# 09_Misc.net
KiCad netlist of a schematic drawn in Altium Designer
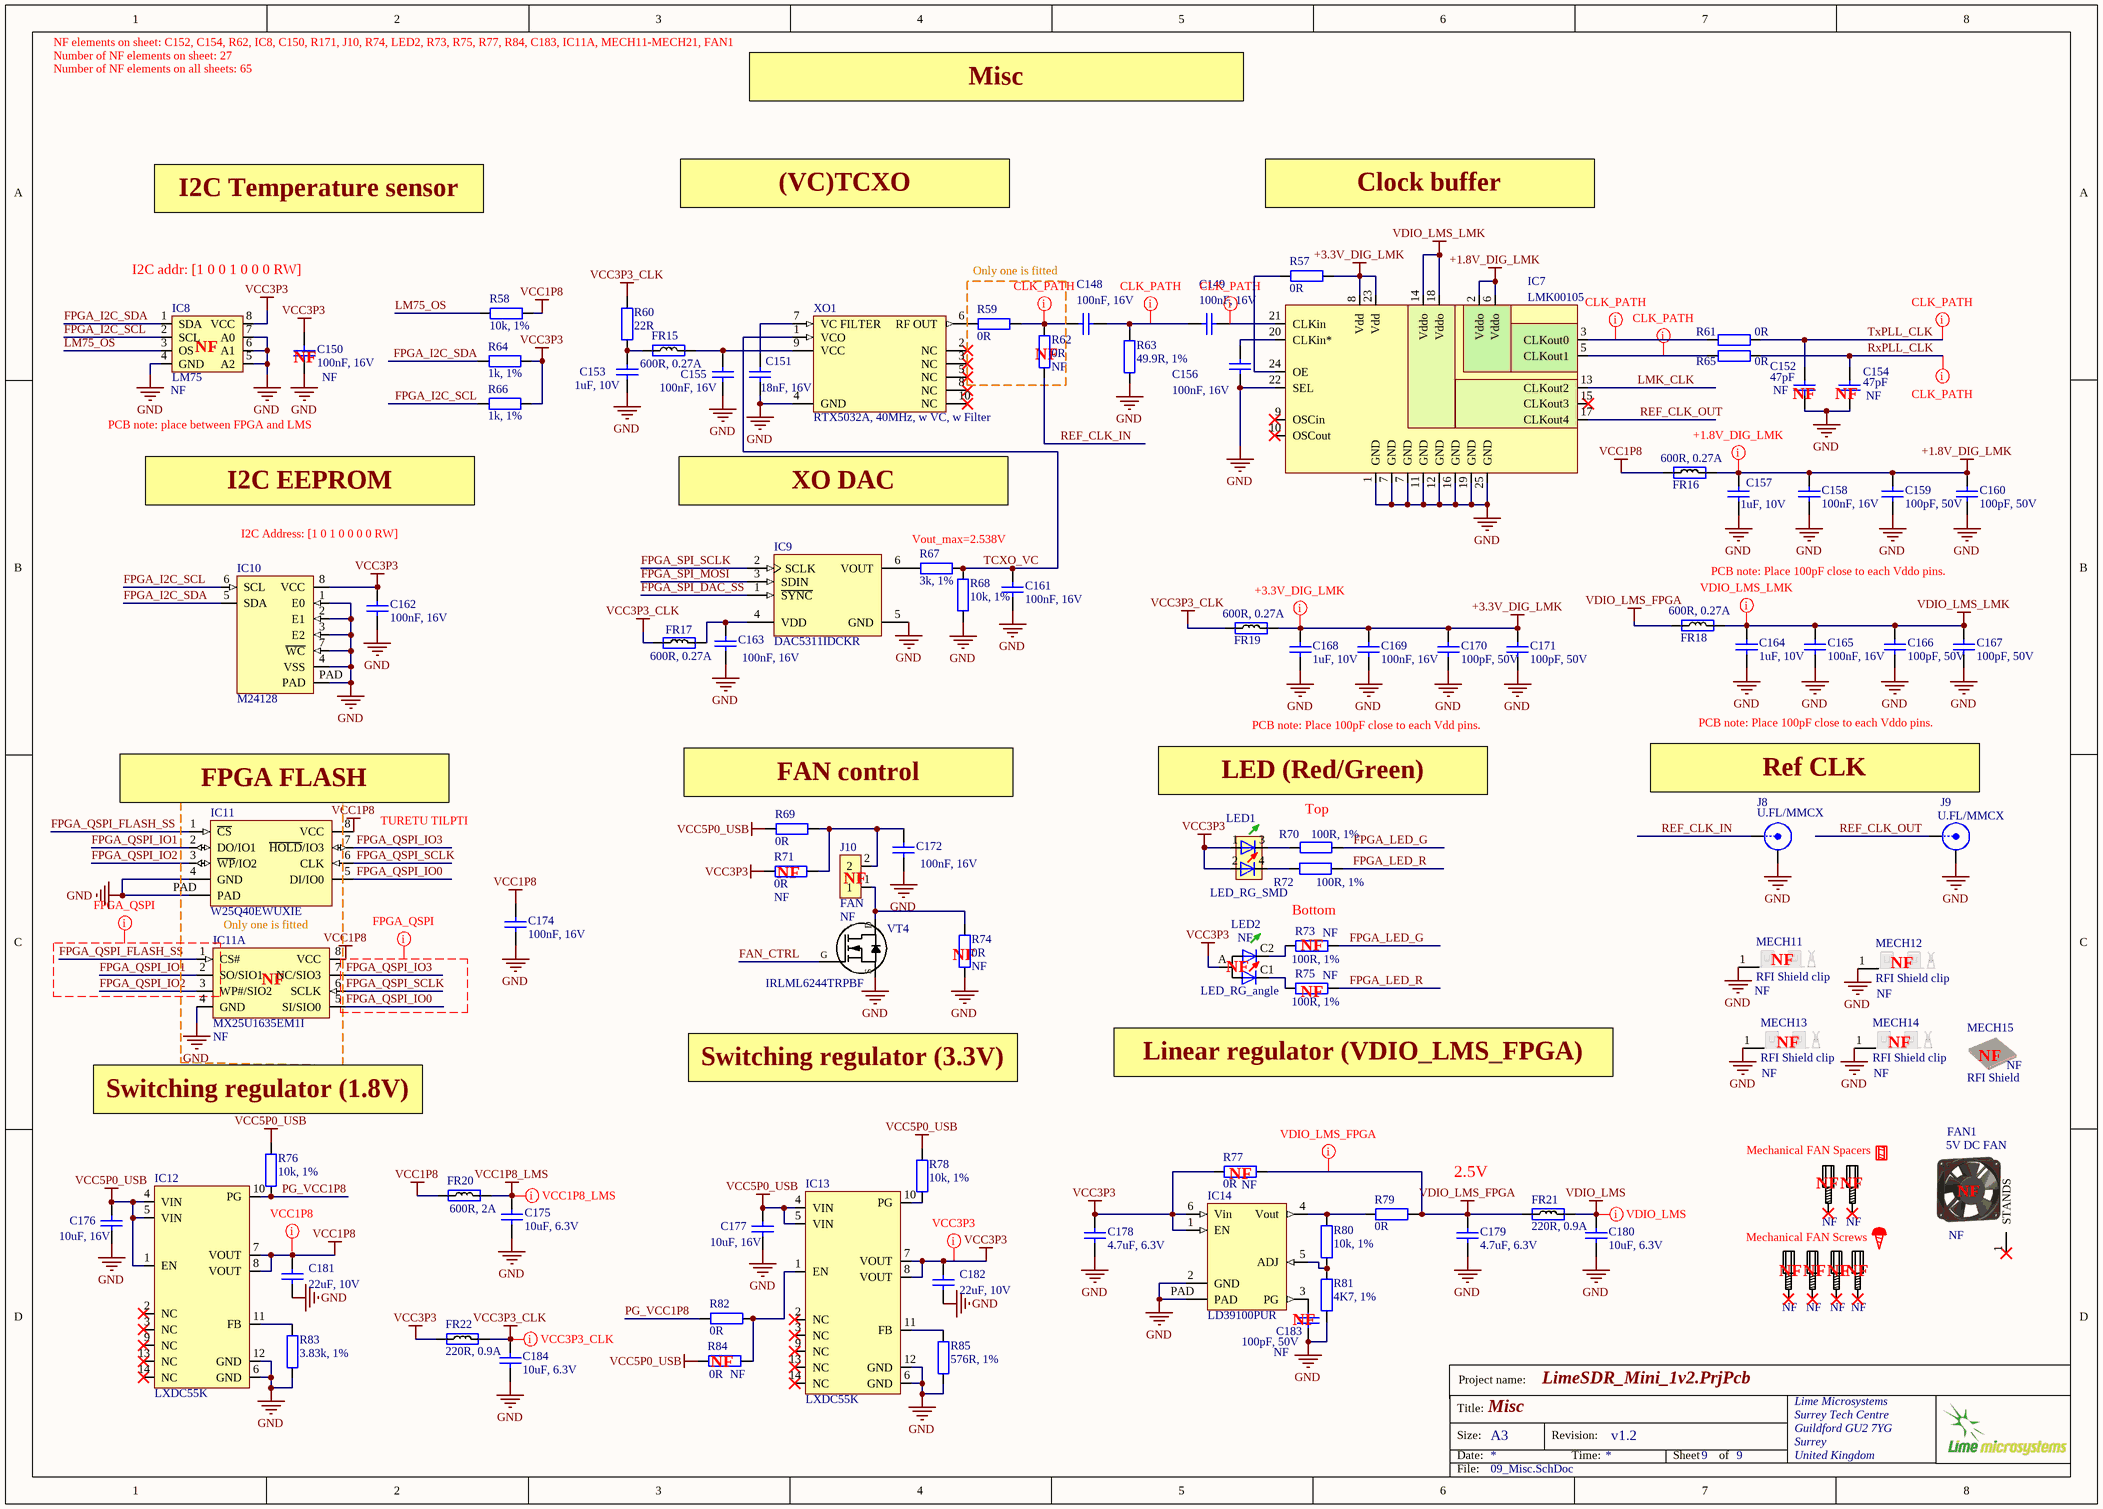
[diagram p0: 09_Misc.SchDoc]

(export (version "E")
  (design (tool "Eeschema 10.0.6"))
  (components
    (comp (ref "C148")
      (value "100nF, 16V")
      (footprint "CAP0402")
      (fields
        (field (name "MANUFACTURER") "Murata Electronics")
        (field (name "TOLERANCE") "10 %")
        (field (name "MANUFACTURER PART NUMBER") "GRM155R71C104KA88D")
      )
      (libsource (lib "LimeMicroAltiumLib_schLib") (part "Cap_0402"))
    )
    (comp (ref "C149")
      (value "100nF, 16V")
      (footprint "CAP0402")
      (fields
        (field (name "MANUFACTURER") "Murata Electronics")
        (field (name "TOLERANCE") "10 %")
        (field (name "MANUFACTURER PART NUMBER") "GRM155R71C104KA88D")
      )
      (libsource (lib "LimeMicroAltiumLib_schLib") (part "Cap_0402"))
    )
    (comp (ref "C150")
      (value "100nF, 16V")
      (footprint "CAP0402")
      (fields
        (field (name "TOLERANCE") "10 %")
        (field (name "MANUFACTURER") "Murata Electronics")
        (field (name "MANUFACTURER PART NUMBER") "GRM155R71C104KA88D")
        (field (name "ASSEMBLY INFO") "NF")
      )
      (libsource (lib "LimeFPGAboard_schLib") (part "Cap_0603"))
    )
    (comp (ref "C151")
      (value "18nF, 16V")
      (footprint "CAP0402")
      (fields (field (name "MANUFACTURER") "Yageo") (field (name "TOLERANCE") "±10%"))
      (libsource (lib "LimeMicroAltiumLib_schLib") (part "Cap_0402"))
    )
    (comp (ref "C152")
      (value "47pF")
      (footprint "CAP0402")
      (fields
        (field (name "TOLERANCE") "±1%")
        (field (name "MANUFACTURER") "TDK Corporation")
        (field (name "ASSEMBLY INFO") "NF")
      )
      (libsource (lib "LimeMicroAltiumLib_schLib") (part "Cap_0402"))
    )
    (comp (ref "C153")
      (value "1uF, 10V")
      (footprint "CAP0402")
      (fields (field (name "MANUFACTURER") "TDK"))
      (libsource (lib "LimeMicroAltiumLib_schLib") (part "Cap_0402"))
    )
    (comp (ref "C154")
      (value "47pF")
      (footprint "CAP0402")
      (fields
        (field (name "TOLERANCE") "±1%")
        (field (name "MANUFACTURER") "TDK Corporation")
        (field (name "ASSEMBLY INFO") "NF")
      )
      (libsource (lib "LimeMicroAltiumLib_schLib") (part "Cap_0402"))
    )
    (comp (ref "C155")
      (value "100nF, 16V")
      (footprint "CAP0402")
      (fields
        (field (name "MANUFACTURER") "Murata Electronics")
        (field (name "TOLERANCE") "10 %")
        (field (name "MANUFACTURER PART NUMBER") "GRM155R71C104KA88D")
      )
      (libsource (lib "LimeMicroAltiumLib_schLib") (part "Cap_0402"))
    )
    (comp (ref "C156")
      (value "100nF, 16V")
      (footprint "CAP0402")
      (fields
        (field (name "MANUFACTURER") "Murata Electronics")
        (field (name "TOLERANCE") "10 %")
        (field (name "MANUFACTURER PART NUMBER") "GRM155R71C104KA88D")
      )
      (libsource (lib "LimeMicroAltiumLib_schLib") (part "Cap_0402"))
    )
    (comp (ref "C157")
      (value "1uF, 10V")
      (footprint "CAP0402")
      (fields (field (name "MANUFACTURER") "TDK"))
      (libsource (lib "LimeMicroAltiumLib_schLib") (part "Cap_0402"))
    )
    (comp (ref "C158")
      (value "100nF, 16V")
      (footprint "CAP0402")
      (fields
        (field (name "MANUFACTURER") "Murata Electronics")
        (field (name "TOLERANCE") "10 %")
        (field (name "MANUFACTURER PART NUMBER") "GRM155R71C104KA88D")
      )
      (libsource (lib "LimeMicroAltiumLib_schLib") (part "Cap_0402"))
    )
    (comp (ref "C159")
      (value "100pF, 50V")
      (footprint "CAP0402")
      (fields (field (name "MANUFACTURER") "Yageo") (field (name "TOLERANCE") "±5%"))
      (libsource (lib "LimeMicroAltiumLib_schLib") (part "Cap_0402"))
    )
    (comp (ref "C160")
      (value "100pF, 50V")
      (footprint "CAP0402")
      (fields (field (name "MANUFACTURER") "Yageo") (field (name "TOLERANCE") "±5%"))
      (libsource (lib "LimeMicroAltiumLib_schLib") (part "Cap_0402"))
    )
    (comp (ref "C161")
      (value "100nF, 16V")
      (footprint "CAP0402")
      (fields
        (field (name "MANUFACTURER") "Murata Electronics")
        (field (name "TOLERANCE") "10 %")
        (field (name "MANUFACTURER PART NUMBER") "GRM155R71C104KA88D")
      )
      (libsource (lib "LimeMicroAltiumLib_schLib") (part "Cap_0402"))
    )
    (comp (ref "C162")
      (value "100nF, 16V")
      (footprint "CAP0402")
      (fields
        (field (name "TOLERANCE") "10 %")
        (field (name "MANUFACTURER") "Murata Electronics")
        (field (name "MANUFACTURER PART NUMBER") "GRM155R71C104KA88D")
      )
      (libsource (lib "LimeFPGAboard_schLib") (part "Cap_0603"))
    )
    (comp (ref "C163")
      (value "100nF, 16V")
      (footprint "CAP0402")
      (fields
        (field (name "TOLERANCE") "10 %")
        (field (name "MANUFACTURER") "Murata Electronics")
        (field (name "MANUFACTURER PART NUMBER") "GRM155R71C104KA88D")
      )
      (libsource (lib "LimeFPGAboard_schLib") (part "Cap_0603"))
    )
    (comp (ref "C164")
      (value "1uF, 10V")
      (footprint "CAP0402")
      (fields (field (name "MANUFACTURER") "TDK"))
      (libsource (lib "LimeMicroAltiumLib_schLib") (part "Cap_0402"))
    )
    (comp (ref "C165")
      (value "100nF, 16V")
      (footprint "CAP0402")
      (fields
        (field (name "MANUFACTURER") "Murata Electronics")
        (field (name "TOLERANCE") "10 %")
        (field (name "MANUFACTURER PART NUMBER") "GRM155R71C104KA88D")
      )
      (libsource (lib "LimeMicroAltiumLib_schLib") (part "Cap_0402"))
    )
    (comp (ref "C166")
      (value "100pF, 50V")
      (footprint "CAP0402")
      (fields (field (name "MANUFACTURER") "Yageo") (field (name "TOLERANCE") "±5%"))
      (libsource (lib "LimeMicroAltiumLib_schLib") (part "Cap_0402"))
    )
    (comp (ref "C167")
      (value "100pF, 50V")
      (footprint "CAP0402")
      (fields (field (name "MANUFACTURER") "Yageo") (field (name "TOLERANCE") "±5%"))
      (libsource (lib "LimeMicroAltiumLib_schLib") (part "Cap_0402"))
    )
    (comp (ref "C168")
      (value "1uF, 10V")
      (footprint "CAP0402")
      (fields (field (name "MANUFACTURER") "TDK"))
      (libsource (lib "LimeMicroAltiumLib_schLib") (part "Cap_0402"))
    )
    (comp (ref "C169")
      (value "100nF, 16V")
      (footprint "CAP0402")
      (fields
        (field (name "MANUFACTURER") "Murata Electronics")
        (field (name "TOLERANCE") "10 %")
        (field (name "MANUFACTURER PART NUMBER") "GRM155R71C104KA88D")
      )
      (libsource (lib "LimeMicroAltiumLib_schLib") (part "Cap_0402"))
    )
    (comp (ref "C170")
      (value "100pF, 50V")
      (footprint "CAP0402")
      (fields (field (name "MANUFACTURER") "Yageo") (field (name "TOLERANCE") "±5%"))
      (libsource (lib "LimeMicroAltiumLib_schLib") (part "Cap_0402"))
    )
    (comp (ref "C171")
      (value "100pF, 50V")
      (footprint "CAP0402")
      (fields (field (name "MANUFACTURER") "Yageo") (field (name "TOLERANCE") "±5%"))
      (libsource (lib "LimeMicroAltiumLib_schLib") (part "Cap_0402"))
    )
    (comp (ref "C172")
      (value "100nF, 16V")
      (footprint "CAP0402")
      (fields
        (field (name "TOLERANCE") "10 %")
        (field (name "MANUFACTURER") "Murata Electronics")
        (field (name "MANUFACTURER PART NUMBER") "GRM155R71C104KA88D")
      )
      (libsource (lib "LimeFPGAboard_schLib") (part "Cap_0603"))
    )
    (comp (ref "C174")
      (value "100nF, 16V")
      (footprint "CAP0402")
      (fields
        (field (name "TOLERANCE") "10 %")
        (field (name "MANUFACTURER") "Murata Electronics")
        (field (name "MANUFACTURER PART NUMBER") "GRM155R71C104KA88D")
      )
      (libsource (lib "LimeFPGAboard_schLib") (part "Cap_0603"))
    )
    (comp (ref "C175")
      (value "10uF, 6.3V")
      (footprint "CAP0603")
      (fields (field (name "TOLERANCE") "±20%") (field (name "MANUFACTURER") "Yageo"))
      (libsource (lib "LimeFPGAboard_schLib") (part "Cap_0603"))
    )
    (comp (ref "C176")
      (value "10uF, 16V")
      (footprint "CAP0603")
      (fields (field (name "MANUFACTURER") "Yageo") (field (name "TOLERANCE") "±20%"))
      (libsource (lib "LimeMicroAltiumLib_schLib") (part "Cap_0603"))
    )
    (comp (ref "C177")
      (value "10uF, 16V")
      (footprint "CAP0603")
      (fields (field (name "MANUFACTURER") "Yageo") (field (name "TOLERANCE") "±20%"))
      (libsource (lib "LimeMicroAltiumLib_schLib") (part "Cap_0603"))
    )
    (comp (ref "C178")
      (value "4.7uF, 6.3V")
      (footprint "CAP0402")
      (fields
        (field (name "MANUFACTURER") "Murata Electronics North America")
        (field (name "TOLERANCE") "±20%")
        (field (name "MANUFACTURER PART NUMBER") "GRM155R60J475ME87D")
      )
      (libsource (lib "LimeMicroAltiumLib_schLib") (part "Cap_0402"))
    )
    (comp (ref "C179")
      (value "4.7uF, 6.3V")
      (footprint "CAP0402")
      (fields
        (field (name "MANUFACTURER") "Murata Electronics North America")
        (field (name "TOLERANCE") "±20%")
        (field (name "MANUFACTURER PART NUMBER") "GRM155R60J475ME87D")
      )
      (libsource (lib "LimeMicroAltiumLib_schLib") (part "Cap_0402"))
    )
    (comp (ref "C180")
      (value "10uF, 6.3V")
      (footprint "CAP0603")
      (fields (field (name "TOLERANCE") "±20%") (field (name "MANUFACTURER") "Yageo"))
      (libsource (lib "LimeFPGAboard_schLib") (part "Cap_0603"))
    )
    (comp (ref "C181")
      (value "22uF, 10V")
      (footprint "CAP0603")
      (fields (field (name "TOLERANCE") "20 %") (field (name "MANUFACTURER") "TDK Corporation"))
      (libsource (lib "LimeFPGAboard_schLib") (part "Cap_0603"))
    )
    (comp (ref "C182")
      (value "22uF, 10V")
      (footprint "CAP0603")
      (fields (field (name "TOLERANCE") "20 %") (field (name "MANUFACTURER") "TDK Corporation"))
      (libsource (lib "LimeFPGAboard_schLib") (part "Cap_0603"))
    )
    (comp (ref "C183")
      (value "100pF, 50V")
      (footprint "CAP0402")
      (fields
        (field (name "ASSEMBLY INFO") "NF")
        (field (name "MANUFACTURER") "Yageo")
        (field (name "TOLERANCE") "±5%")
      )
      (libsource (lib "LimeMicroAltiumLib_schLib") (part "Cap_0402"))
    )
    (comp (ref "C184")
      (value "10uF, 6.3V")
      (footprint "CAP0603")
      (fields (field (name "TOLERANCE") "±20%") (field (name "MANUFACTURER") "Yageo"))
      (libsource (lib "LimeFPGAboard_schLib") (part "Cap_0603"))
    )
    (comp (ref "FAN1")
      (value "5V DC FAN")
      (fields
        (field (name "MANUFACTURER") "Sunon Fans")
        (field (name "MANUFACTURER PART NUMBER") "MC30060V2-000U-A99")
        (field (name "ASSEMBLY INFO") "NF")
      )
      (libsource (lib "LimeMicroAltiumLib_schLib") (part "12V_DC_FAN"))
    )
    (comp (ref "FR15")
      (value "600R, 0.27A")
      (footprint "RES0201")
      (fields (field (name "MANUFACTURER") "Taiyo Yuden"))
      (libsource (lib "LimeMicroAltiumLib_schLib") (part "Ferrite"))
    )
    (comp (ref "FR16")
      (value "600R, 0.27A")
      (footprint "RES0201")
      (fields (field (name "MANUFACTURER") "Taiyo Yuden"))
      (libsource (lib "LimeMicroAltiumLib_schLib") (part "Ferrite"))
    )
    (comp (ref "FR17")
      (value "600R, 0.27A")
      (footprint "RES0201")
      (fields (field (name "MANUFACTURER") "Taiyo Yuden"))
      (libsource (lib "LimeMicroAltiumLib_schLib") (part "Ferrite"))
    )
    (comp (ref "FR18")
      (value "600R, 0.27A")
      (footprint "RES0201")
      (fields (field (name "MANUFACTURER") "Taiyo Yuden"))
      (libsource (lib "LimeMicroAltiumLib_schLib") (part "Ferrite"))
    )
    (comp (ref "FR19")
      (value "600R, 0.27A")
      (footprint "RES0201")
      (fields (field (name "MANUFACTURER") "Taiyo Yuden"))
      (libsource (lib "LimeMicroAltiumLib_schLib") (part "Ferrite"))
    )
    (comp (ref "FR20")
      (value "600R, 2A")
      (footprint "RES0805")
      (fields (field (name "MANUFACTURER") "TDK Corporation"))
      (libsource (lib "LimeMicroAltiumLib_schLib") (part "Ferrite"))
    )
    (comp (ref "FR21")
      (value "220R, 0.9A")
      (footprint "RES0402")
      (fields (field (name "MANUFACTURER") "TDK Corporation"))
      (libsource (lib "LimeFPGAboard_schLib") (part "Ferrite"))
    )
    (comp (ref "FR22")
      (value "220R, 0.9A")
      (footprint "RES0402")
      (fields (field (name "MANUFACTURER") "TDK Corporation"))
      (libsource (lib "LimeFPGAboard_schLib") (part "Ferrite"))
    )
    (comp (ref "IC7")
      (value "LMK00105")
      (footprint "LMK00105SQ")
      (fields (field (name "MANUFACTURER") "Texas Instruments"))
      (libsource (lib "LimeMicroAltiumLib_schLib") (part "LMK00105"))
    )
    (comp (ref "IC8")
      (value "LM75")
      (footprint "HWSON8_LM75")
      (fields
        (field (name "MANUFACTURER") "NXP Semiconductors")
        (field (name "MANUFACTURER PART NUMBER") "LM75BTP,147")
        (field (name "ASSEMBLY INFO") "NF")
      )
      (libsource (lib "LimeMicroAltiumLib_schLib") (part "LM75"))
    )
    (comp (ref "IC9")
      (value "DAC5311IDCKR")
      (footprint "AD5601_SOT23-6")
      (fields (field (name "MANUFACTURER") "Texas Instruments"))
      (libsource (lib "LimeMicroAltiumLib_schLib") (part "AD5601BKSZ-REEL7"))
    )
    (comp (ref "IC10")
      (value "M24128")
      (footprint "M24128-DFMC6TG")
      (fields (field (name "MANUFACTURER") "STMicroelectronics"))
      (libsource (lib "LimeMicroAltiumLib_schLib") (part "M24128-DFMC6TG"))
    )
    (comp (ref "IC11")
      (value "W25Q40EWUXIE")
      (footprint "W25Q40EWUXIE_8-USON")
      (fields (field (name "MANUFACTURER") "Winbond Electronics"))
      (libsource (lib "LimeMicroAltiumLib_schLib") (part "W25Q40EWUXIE"))
    )
    (comp (ref "IC11A")
      (value "MX25U1635EM1I")
      (footprint "MX25U1635EM1I-10G_SOP8_150mil")
      (fields
        (field (name "MANUFACTURER") "Macronix")
        (field (name "MANUFACTURER PART NUMBER") "MX25U1635EM1I-10G")
        (field (name "ASSEMBLY INFO") "NF")
      )
      (libsource (lib "LimeMicroAltiumLib_schLib") (part "MX25U1635EM1I-10G"))
    )
    (comp (ref "IC12")
      (value "LXDC55K")
      (footprint "LXDC55K")
      (description "LXDC55KAAA-205")
      (fields (field (name "MANUFACTURER") "Murata Electronics North America"))
      (libsource (lib "LimeMicroAltiumLib_schLib") (part "LXDC55K"))
    )
    (comp (ref "IC13")
      (value "LXDC55K")
      (footprint "LXDC55K")
      (description "LXDC55KAAA-205")
      (fields (field (name "MANUFACTURER") "Murata Electronics North America"))
      (libsource (lib "LimeMicroAltiumLib_schLib") (part "LXDC55K"))
    )
    (comp (ref "IC14")
      (value "LD39100PUR")
      (footprint "LD39100PUR")
      (fields (field (name "MANUFACTURER") "STMicroelectronics"))
      (libsource (lib "LimeMicroAltiumLib_schLib") (part "LD39100PUR"))
    )
    (comp (ref "J8")
      (value "U.FL/MMCX")
      (footprint "MMCX_UFL_conn_u")
      (description "CONN UMC RCPT STR 50 OHM SMD")
      (fields (field (name "MANUFACTURER") "Molex, LLC"))
      (libsource (lib "LimeMicroAltiumLib_schLib") (part "RF_IF_connector"))
    )
    (comp (ref "J9")
      (value "U.FL/MMCX")
      (footprint "MMCX_UFL_conn_u")
      (description "CONN UMC RCPT STR 50 OHM SMD")
      (fields (field (name "MANUFACTURER") "Molex, LLC"))
      (libsource (lib "LimeMicroAltiumLib_schLib") (part "RF_IF_connector"))
    )
    (comp (ref "J10")
      (value "FAN")
      (footprint "Header2x1_TH_v2")
      (fields (field (name "ASSEMBLY INFO") "NF") (field (name "MANUFACTURER") "3M"))
      (libsource (lib "LimeFPGAboard_schLib") (part "Jumper"))
    )
    (comp (ref "LED1")
      (value "LED_RG_SMD")
      (footprint "LED-2x0603")
      (fields (field (name "MANUFACTURER") "Avago Technologies US Inc."))
      (libsource (lib "LimeMicroAltiumLib_schLib") (part "LED_green_red_SMD"))
    )
    (comp (ref "LED2")
      (value "LED_RG_angle")
      (footprint "LED_RG_RIGHT_ANGLE_v2")
      (description "160-2033-1-ND")
      (fields (field (name "MANUFACTURER") "Lite-On") (field (name "ASSEMBLY INFO") "NF"))
      (libsource (lib "LimeMicroAltiumLib_schLib") (part "LED_green_red_right_angle"))
    )
    (comp (ref "MECH11")
      (value "RFI Shield clip")
      (footprint "RFI_SHIELD_CLPS_MINI")
      (fields (field (name "MANUFACTURER") "HARWIN") (field (name "ASSEMBLY INFO") "NF"))
      (libsource (lib "LimeMicroAltiumLib_schLib") (part "RFI_SHIELD_CLIP"))
    )
    (comp (ref "MECH12")
      (value "RFI Shield clip")
      (footprint "RFI_SHIELD_CLPS_MINI")
      (fields (field (name "MANUFACTURER") "HARWIN") (field (name "ASSEMBLY INFO") "NF"))
      (libsource (lib "LimeMicroAltiumLib_schLib") (part "RFI_SHIELD_CLIP"))
    )
    (comp (ref "MECH13")
      (value "RFI Shield clip")
      (footprint "RFI_SHIELD_CLPS_MINI")
      (fields (field (name "MANUFACTURER") "HARWIN") (field (name "ASSEMBLY INFO") "NF"))
      (libsource (lib "LimeMicroAltiumLib_schLib") (part "RFI_SHIELD_CLIP"))
    )
    (comp (ref "MECH14")
      (value "RFI Shield clip")
      (footprint "RFI_SHIELD_CLPS_MINI")
      (fields (field (name "MANUFACTURER") "HARWIN") (field (name "ASSEMBLY INFO") "NF"))
      (libsource (lib "LimeMicroAltiumLib_schLib") (part "RFI_SHIELD_CLIP"))
    )
    (comp (ref "MECH15")
      (value "RFI Shield")
      (footprint "WurthElectronic_RF_shield")
      (fields (field (name "MANUFACTURER") "WURTH ELEKTRONIK") (field (name "ASSEMBLY INFO") "NF"))
      (libsource (lib "LimeMicroAltiumLib_schLib") (part "RFI_SHIELD_1"))
    )
    (comp (ref "MECH16")
      (value "Spacer M3")
      (description "STANDOFF M/F MET 5MM HEX 10MM L")
      (fields (field (name "MANUFACTURER") "BOSSARD") (field (name "ASSEMBLY INFO") "NF"))
      (libsource (lib "LimeMicroAltiumLib_schLib") (part "STANDOFF_M-F_THREADED_M3x8x10mm_HEX_5mm dia"))
    )
    (comp (ref "MECH17")
      (value "Spacer M3")
      (description "STANDOFF M/F MET 5MM HEX 10MM L")
      (fields (field (name "MANUFACTURER") "BOSSARD") (field (name "ASSEMBLY INFO") "NF"))
      (libsource (lib "LimeMicroAltiumLib_schLib") (part "STANDOFF_M-F_THREADED_M3x8x10mm_HEX_5mm dia"))
    )
    (comp (ref "MECH18")
      (value "Screws M3")
      (description "STANDOFF M/F MET 5MM HEX 10MM L")
      (fields (field (name "MANUFACTURER") "KRAFTBERG") (field (name "ASSEMBLY INFO") "NF"))
      (libsource (lib "LimeMicroAltiumLib_schLib") (part "STANDOFF_M-F_THREADED_M3x8x10mm_HEX_5mm dia"))
    )
    (comp (ref "MECH19")
      (value "Screws M3")
      (description "STANDOFF M/F MET 5MM HEX 10MM L")
      (fields (field (name "MANUFACTURER") "KRAFTBERG") (field (name "ASSEMBLY INFO") "NF"))
      (libsource (lib "LimeMicroAltiumLib_schLib") (part "STANDOFF_M-F_THREADED_M3x8x10mm_HEX_5mm dia"))
    )
    (comp (ref "MECH20")
      (value "Screws M3")
      (description "STANDOFF M/F MET 5MM HEX 10MM L")
      (fields (field (name "MANUFACTURER") "KRAFTBERG") (field (name "ASSEMBLY INFO") "NF"))
      (libsource (lib "LimeMicroAltiumLib_schLib") (part "STANDOFF_M-F_THREADED_M3x8x10mm_HEX_5mm dia"))
    )
    (comp (ref "MECH21")
      (value "Screws M3")
      (description "STANDOFF M/F MET 5MM HEX 10MM L")
      (fields (field (name "MANUFACTURER") "KRAFTBERG") (field (name "ASSEMBLY INFO") "NF"))
      (libsource (lib "LimeMicroAltiumLib_schLib") (part "STANDOFF_M-F_THREADED_M3x8x10mm_HEX_5mm dia"))
    )
    (comp (ref "R57")
      (value "0R")
      (footprint "RES0402")
      (fields (field (name "MANUFACTURER") "Yageo") (field (name "TOLERANCE") "Jumper"))
      (libsource (lib "LimeMicroAltiumLib_schLib") (part "Res_0402"))
    )
    (comp (ref "R58")
      (value "10k, 1%")
      (footprint "RES0402")
      (fields (field (name "MANUFACTURER") "Yageo") (field (name "TOLERANCE") "±1%"))
      (libsource (lib "LimeMicroAltiumLib_schLib") (part "Res_0402"))
    )
    (comp (ref "R59")
      (value "0R")
      (footprint "RES0402")
      (fields (field (name "MANUFACTURER") "Yageo") (field (name "TOLERANCE") "Jumper"))
      (libsource (lib "LimeMicroAltiumLib_schLib") (part "Res_0402"))
    )
    (comp (ref "R60")
      (value "22R")
      (footprint "RES0402")
      (fields (field (name "TOLERANCE") "±1%") (field (name "MANUFACTURER") "Yageo"))
      (libsource (lib "LimeFPGAboard_schLib") (part "Res_0402"))
    )
    (comp (ref "R61")
      (value "0R")
      (footprint "RES0402")
      (fields (field (name "MANUFACTURER") "Yageo"))
      (libsource (lib "LimeFPGAboard_schLib") (part "Res_0402"))
    )
    (comp (ref "R62")
      (value "0R")
      (footprint "RES0402")
      (fields
        (field (name "ASSEMBLY INFO") "NF")
        (field (name "MANUFACTURER") "Yageo")
        (field (name "TOLERANCE") "Jumper")
      )
      (libsource (lib "LimeMicroAltiumLib_schLib") (part "Res_0402"))
    )
    (comp (ref "R63")
      (value "49.9R, 1%")
      (footprint "RES0402")
      (fields
        (field (name "TOLERANCE") "±1%")
        (field (name "MANUFACTURER") "Samsung Electro-Mechanics America, Inc.")
        (field (name "MANUFACTURER PART NUMBER") "RC1005F49R9CS")
      )
      (libsource (lib "LimeMicroAltiumLib_schLib") (part "Res_0402"))
    )
    (comp (ref "R64")
      (value "1k, 1%")
      (footprint "RES0402")
      (fields (field (name "MANUFACTURER") "Stackpole Electronics Inc") (field (name "TOLERANCE") "±1%"))
      (libsource (lib "LimeMicroAltiumLib_schLib") (part "Res_0402"))
    )
    (comp (ref "R65")
      (value "0R")
      (footprint "RES0402")
      (fields (field (name "MANUFACTURER") "Yageo"))
      (libsource (lib "LimeFPGAboard_schLib") (part "Res_0402"))
    )
    (comp (ref "R66")
      (value "1k, 1%")
      (footprint "RES0402")
      (fields (field (name "MANUFACTURER") "Stackpole Electronics Inc") (field (name "TOLERANCE") "±1%"))
      (libsource (lib "LimeMicroAltiumLib_schLib") (part "Res_0402"))
    )
    (comp (ref "R67")
      (value "3k, 1%")
      (footprint "RES0402")
      (fields (field (name "TOLERANCE") "±1%") (field (name "MANUFACTURER") "Vishay Dale"))
      (libsource (lib "LimeMicroAltiumLib_schLib") (part "Res_0402"))
    )
    (comp (ref "R68")
      (value "10k, 1%")
      (footprint "RES0402")
      (fields (field (name "MANUFACTURER") "Yageo") (field (name "TOLERANCE") "±1%"))
      (libsource (lib "LimeMicroAltiumLib_schLib") (part "Res_0402"))
    )
    (comp (ref "R69")
      (value "0R")
      (footprint "RES0402")
      (fields (field (name "MANUFACTURER") "Yageo") (field (name "TOLERANCE") "Jumper"))
      (libsource (lib "LimeMicroAltiumLib_schLib") (part "Res_0402"))
    )
    (comp (ref "R70")
      (value "100R, 1%")
      (footprint "RES0402")
      (fields (field (name "TOLERANCE") "±1%") (field (name "MANUFACTURER") "Stackpole Electronics Inc."))
      (libsource (lib "LimeMicroAltiumLib_schLib") (part "Res_0402"))
    )
    (comp (ref "R71")
      (value "0R")
      (footprint "RES0402")
      (fields
        (field (name "ASSEMBLY INFO") "NF")
        (field (name "MANUFACTURER") "Yageo")
        (field (name "TOLERANCE") "Jumper")
      )
      (libsource (lib "LimeMicroAltiumLib_schLib") (part "Res_0402"))
    )
    (comp (ref "R72")
      (value "100R, 1%")
      (footprint "RES0402")
      (fields (field (name "TOLERANCE") "±1%") (field (name "MANUFACTURER") "Stackpole Electronics Inc."))
      (libsource (lib "LimeMicroAltiumLib_schLib") (part "Res_0402"))
    )
    (comp (ref "R73")
      (value "100R, 1%")
      (footprint "RES0402")
      (fields
        (field (name "TOLERANCE") "±1%")
        (field (name "MANUFACTURER") "Stackpole Electronics Inc.")
        (field (name "ASSEMBLY INFO") "NF")
      )
      (libsource (lib "LimeMicroAltiumLib_schLib") (part "Res_0402"))
    )
    (comp (ref "R74")
      (value "0R")
      (footprint "RES0402")
      (fields
        (field (name "ASSEMBLY INFO") "NF")
        (field (name "MANUFACTURER") "Yageo")
        (field (name "TOLERANCE") "Jumper")
      )
      (libsource (lib "LimeMicroAltiumLib_schLib") (part "Res_0402"))
    )
    (comp (ref "R75")
      (value "100R, 1%")
      (footprint "RES0402")
      (fields
        (field (name "TOLERANCE") "±1%")
        (field (name "MANUFACTURER") "Stackpole Electronics Inc.")
        (field (name "ASSEMBLY INFO") "NF")
      )
      (libsource (lib "LimeMicroAltiumLib_schLib") (part "Res_0402"))
    )
    (comp (ref "R76")
      (value "10k, 1%")
      (footprint "RES0402")
      (fields (field (name "MANUFACTURER") "Yageo") (field (name "TOLERANCE") "±1%"))
      (libsource (lib "LimeMicroAltiumLib_schLib") (part "Res_0402"))
    )
    (comp (ref "R77")
      (value "0R")
      (footprint "RES0402")
      (fields (field (name "MANUFACTURER") "Yageo") (field (name "ASSEMBLY INFO") "NF"))
      (libsource (lib "LimeFPGAboard_schLib") (part "Res_0402"))
    )
    (comp (ref "R78")
      (value "10k, 1%")
      (footprint "RES0402")
      (fields (field (name "MANUFACTURER") "Yageo") (field (name "TOLERANCE") "±1%"))
      (libsource (lib "LimeMicroAltiumLib_schLib") (part "Res_0402"))
    )
    (comp (ref "R79")
      (value "0R")
      (footprint "RES0402")
      (fields (field (name "MANUFACTURER") "Yageo"))
      (libsource (lib "LimeFPGAboard_schLib") (part "Res_0402"))
    )
    (comp (ref "R80")
      (value "10k, 1%")
      (footprint "RES0402")
      (fields (field (name "MANUFACTURER") "Yageo") (field (name "TOLERANCE") "±1%"))
      (libsource (lib "LimeMicroAltiumLib_schLib") (part "Res_0402"))
    )
    (comp (ref "R81")
      (value "4K7, 1%")
      (footprint "RES0402")
      (fields (field (name "MANUFACTURER") "Yageo") (field (name "TOLERANCE") "±1%"))
      (libsource (lib "LimeFPGAboard_schLib") (part "Res_0402"))
    )
    (comp (ref "R82")
      (value "0R")
      (footprint "RES0402")
      (fields (field (name "MANUFACTURER") "Yageo") (field (name "TOLERANCE") "Jumper"))
      (libsource (lib "LimeMicroAltiumLib_schLib") (part "Res_0402"))
    )
    (comp (ref "R83")
      (value "3.83k, 1%")
      (footprint "RES0402")
      (fields (field (name "TOLERANCE") "±1%") (field (name "MANUFACTURER") "Stackpole Electronics Inc."))
      (libsource (lib "LimeMicroAltiumLib_schLib") (part "Res_0402"))
    )
    (comp (ref "R84")
      (value "0R")
      (footprint "RES0402")
      (fields
        (field (name "ASSEMBLY INFO") "NF")
        (field (name "MANUFACTURER") "Yageo")
        (field (name "TOLERANCE") "Jumper")
      )
      (libsource (lib "LimeMicroAltiumLib_schLib") (part "Res_0402"))
    )
    (comp (ref "R85")
      (value "576R, 1%")
      (footprint "RES0402")
      (fields (field (name "TOLERANCE") "±1%") (field (name "MANUFACTURER") "Yageo"))
      (libsource (lib "LimeMicroAltiumLib_schLib") (part "Res_0402"))
    )
    (comp (ref "VT4")
      (value "IRLML6244TRPBF")
      (footprint "SOT23-3")
      (description "NDS331N")
      (fields (field (name "MANUFACTURER") "Infineon Technologies"))
      (libsource (lib "LimeFPGAboard_schLib") (part "NDS331N"))
    )
    (comp (ref "XO1")
      (value "RTX5032A, 40MHz, w VC, w Filter")
      (footprint "RAKON_RTX5032A")
      (fields (field (name "MANUFACTURER") "Rakon"))
      (libsource (lib "LimeMicroAltiumLib_schLib") (part "Rakon_RTX5032A"))
    )
  )
  (nets
    (net (code "1") (name "+1.8V_DIG_LMK") (class "Default")
      (node (ref "C157") (pin "2") (pinfunction "2_2") (pintype "passive"))
      (node (ref "C158") (pin "2") (pinfunction "2_2") (pintype "passive"))
      (node (ref "C159") (pin "2") (pinfunction "2_2") (pintype "passive"))
      (node (ref "C160") (pin "2") (pinfunction "2_2") (pintype "passive"))
      (node (ref "FR16") (pin "2") (pinfunction "2_2") (pintype "passive"))
      (node (ref "IC7") (pin "2") (pinfunction "Vddo_2") (pintype "passive"))
      (node (ref "IC7") (pin "6") (pinfunction "Vddo_6") (pintype "passive"))
    )
    (net (code "2") (name "+3.3V_DIG_LMK") (class "Default")
      (node (ref "C168") (pin "2") (pinfunction "2_2") (pintype "passive"))
      (node (ref "C169") (pin "2") (pinfunction "2_2") (pintype "passive"))
      (node (ref "C170") (pin "2") (pinfunction "2_2") (pintype "passive"))
      (node (ref "C171") (pin "2") (pinfunction "2_2") (pintype "passive"))
      (node (ref "FR19") (pin "2") (pinfunction "2_2") (pintype "passive"))
      (node (ref "IC7") (pin "23") (pinfunction "Vdd_23") (pintype "passive"))
      (node (ref "IC7") (pin "8") (pinfunction "Vdd_8") (pintype "passive"))
      (node (ref "R57") (pin "2") (pinfunction "2_2") (pintype "passive"))
    )
    (net (code "3") (name "/FAN_CTRL") (class "Default")
      (node (ref "VT4") (pin "G") (pinfunction "G_G") (pintype "passive"))
    )
    (net (code "4") (name "/FPGA_I2C_SCL") (class "Default")
      (node (ref "IC10") (pin "6") (pinfunction "SCL_6") (pintype "input"))
      (node (ref "IC8") (pin "2") (pinfunction "SCL_2") (pintype "passive"))
      (node (ref "R66") (pin "2") (pinfunction "2_2") (pintype "passive"))
    )
    (net (code "5") (name "/FPGA_I2C_SDA") (class "Default")
      (node (ref "IC10") (pin "5") (pinfunction "SDA_5") (pintype "bidirectional"))
      (node (ref "IC8") (pin "1") (pinfunction "SDA_1") (pintype "passive"))
      (node (ref "R64") (pin "2") (pinfunction "2_2") (pintype "passive"))
    )
    (net (code "6") (name "/FPGA_LED_G") (class "Default")
      (node (ref "R70") (pin "2") (pinfunction "2_2") (pintype "passive"))
      (node (ref "R73") (pin "2") (pinfunction "2_2") (pintype "passive"))
    )
    (net (code "7") (name "/FPGA_LED_R") (class "Default")
      (node (ref "R72") (pin "2") (pinfunction "2_2") (pintype "passive"))
      (node (ref "R75") (pin "2") (pinfunction "2_2") (pintype "passive"))
    )
    (net (code "8") (name "/FPGA_QSPI_FLASH_SS") (class "Default")
      (node (ref "IC11") (pin "1") (pinfunction "~{CS}_1") (pintype "input"))
      (node (ref "IC11A") (pin "1") (pinfunction "CS#_1") (pintype "input"))
    )
    (net (code "9") (name "/FPGA_QSPI_IO0") (class "Default")
      (node (ref "IC11") (pin "5") (pinfunction "DI/IO0_5") (pintype "passive"))
      (node (ref "IC11A") (pin "5") (pinfunction "SI/SIO0_5") (pintype "bidirectional"))
    )
    (net (code "10") (name "/FPGA_QSPI_IO1") (class "Default")
      (node (ref "IC11") (pin "2") (pinfunction "DO/IO1_2") (pintype "bidirectional"))
      (node (ref "IC11A") (pin "2") (pinfunction "SO/SIO1_2") (pintype "bidirectional"))
    )
    (net (code "11") (name "/FPGA_QSPI_IO2") (class "Default")
      (node (ref "IC11") (pin "3") (pinfunction "~{WP}/IO2_3") (pintype "bidirectional"))
      (node (ref "IC11A") (pin "3") (pinfunction "WP#/SIO2_3") (pintype "bidirectional"))
    )
    (net (code "12") (name "/FPGA_QSPI_IO3") (class "Default")
      (node (ref "IC11") (pin "7") (pinfunction "~{HOLD}/IO3_7") (pintype "bidirectional"))
      (node (ref "IC11A") (pin "7") (pinfunction "NC/SIO3_7") (pintype "bidirectional"))
    )
    (net (code "13") (name "/FPGA_QSPI_SCLK") (class "Default")
      (node (ref "IC11") (pin "6") (pinfunction "CLK_6") (pintype "input"))
      (node (ref "IC11A") (pin "6") (pinfunction "SCLK_6") (pintype "input"))
    )
    (net (code "14") (name "/FPGA_SPI_DAC_SS") (class "Default")
      (node (ref "IC9") (pin "1") (pinfunction "~{SYNC}_1") (pintype "input"))
    )
    (net (code "15") (name "/FPGA_SPI_MOSI") (class "Default")
      (node (ref "IC9") (pin "3") (pinfunction "SDIN_3") (pintype "input"))
    )
    (net (code "16") (name "/FPGA_SPI_SCLK") (class "Default")
      (node (ref "IC9") (pin "2") (pinfunction "SCLK_2") (pintype "input"))
    )
    (net (code "17") (name "/LM75_OS") (class "Default")
      (node (ref "IC8") (pin "3") (pinfunction "OS_3") (pintype "passive"))
      (node (ref "R58") (pin "1") (pinfunction "1_1") (pintype "passive"))
    )
    (net (code "18") (name "/LMK_CLK") (class "Default")
      (node (ref "IC7") (pin "13") (pinfunction "CLKout2_13") (pintype "passive"))
    )
    (net (code "19") (name "/PG_VCC1P8") (class "Default")
      (node (ref "IC12") (pin "10") (pinfunction "PG_10") (pintype "passive"))
      (node (ref "R76") (pin "1") (pinfunction "1_1") (pintype "passive"))
      (node (ref "R82") (pin "2") (pinfunction "2_2") (pintype "passive"))
    )
    (net (code "20") (name "/REF_CLK_IN") (class "Default")
      (node (ref "J8") (pin "1") (pinfunction "X_1") (pintype "passive"))
      (node (ref "R62") (pin "1") (pinfunction "1_1") (pintype "passive"))
    )
    (net (code "21") (name "/REF_CLK_OUT") (class "Default")
      (node (ref "IC7") (pin "17") (pinfunction "CLKout4_17") (pintype "passive"))
      (node (ref "J9") (pin "1") (pinfunction "X_1") (pintype "passive"))
    )
    (net (code "22") (name "/RxPLL_CLK") (class "Default")
      (node (ref "C154") (pin "2") (pinfunction "2_2") (pintype "passive"))
      (node (ref "R65") (pin "1") (pinfunction "1_1") (pintype "passive"))
    )
    (net (code "23") (name "/TCXO_VC") (class "Default")
      (node (ref "C161") (pin "2") (pinfunction "2_2") (pintype "passive"))
      (node (ref "R67") (pin "1") (pinfunction "1_1") (pintype "passive"))
      (node (ref "R68") (pin "1") (pinfunction "1_1") (pintype "passive"))
      (node (ref "XO1") (pin "1") (pinfunction "VCO_1") (pintype "input"))
    )
    (net (code "24") (name "/TxPLL_CLK") (class "Default")
      (node (ref "C152") (pin "2") (pinfunction "2_2") (pintype "passive"))
      (node (ref "R61") (pin "1") (pinfunction "1_1") (pintype "passive"))
    )
    (net (code "25") (name "GND") (class "Default")
      (node (ref "C150") (pin "2") (pinfunction "2_2") (pintype "passive"))
      (node (ref "C151") (pin "1") (pinfunction "1_1") (pintype "passive"))
      (node (ref "C152") (pin "1") (pinfunction "1_1") (pintype "passive"))
      (node (ref "C153") (pin "1") (pinfunction "1_1") (pintype "passive"))
      (node (ref "C154") (pin "1") (pinfunction "1_1") (pintype "passive"))
      (node (ref "C155") (pin "1") (pinfunction "1_1") (pintype "passive"))
      (node (ref "C156") (pin "1") (pinfunction "1_1") (pintype "passive"))
      (node (ref "C157") (pin "1") (pinfunction "1_1") (pintype "passive"))
      (node (ref "C158") (pin "1") (pinfunction "1_1") (pintype "passive"))
      (node (ref "C159") (pin "1") (pinfunction "1_1") (pintype "passive"))
      (node (ref "C160") (pin "1") (pinfunction "1_1") (pintype "passive"))
      (node (ref "C161") (pin "1") (pinfunction "1_1") (pintype "passive"))
      (node (ref "C162") (pin "2") (pinfunction "2_2") (pintype "passive"))
      (node (ref "C163") (pin "2") (pinfunction "2_2") (pintype "passive"))
      (node (ref "C164") (pin "1") (pinfunction "1_1") (pintype "passive"))
      (node (ref "C165") (pin "1") (pinfunction "1_1") (pintype "passive"))
      (node (ref "C166") (pin "1") (pinfunction "1_1") (pintype "passive"))
      (node (ref "C167") (pin "1") (pinfunction "1_1") (pintype "passive"))
      (node (ref "C168") (pin "1") (pinfunction "1_1") (pintype "passive"))
      (node (ref "C169") (pin "1") (pinfunction "1_1") (pintype "passive"))
      (node (ref "C170") (pin "1") (pinfunction "1_1") (pintype "passive"))
      (node (ref "C171") (pin "1") (pinfunction "1_1") (pintype "passive"))
      (node (ref "C172") (pin "2") (pinfunction "2_2") (pintype "passive"))
      (node (ref "C174") (pin "2") (pinfunction "2_2") (pintype "passive"))
      (node (ref "C175") (pin "1") (pinfunction "1_1") (pintype "passive"))
      (node (ref "C176") (pin "1") (pinfunction "1_1") (pintype "passive"))
      (node (ref "C177") (pin "1") (pinfunction "1_1") (pintype "passive"))
      (node (ref "C178") (pin "1") (pinfunction "1_1") (pintype "passive"))
      (node (ref "C179") (pin "1") (pinfunction "1_1") (pintype "passive"))
      (node (ref "C180") (pin "1") (pinfunction "1_1") (pintype "passive"))
      (node (ref "C181") (pin "1") (pinfunction "1_1") (pintype "passive"))
      (node (ref "C182") (pin "1") (pinfunction "1_1") (pintype "passive"))
      (node (ref "C183") (pin "1") (pinfunction "1_1") (pintype "passive"))
      (node (ref "C184") (pin "1") (pinfunction "1_1") (pintype "passive"))
      (node (ref "IC10") (pin "1") (pinfunction "E0_1") (pintype "input"))
      (node (ref "IC10") (pin "2") (pinfunction "E1_2") (pintype "input"))
      (node (ref "IC10") (pin "3") (pinfunction "E2_3") (pintype "input"))
      (node (ref "IC10") (pin "4") (pinfunction "VSS_4") (pintype "power_in"))
      (node (ref "IC10") (pin "7") (pinfunction "~{WC}_7") (pintype "input"))
      (node (ref "IC10") (pin "PAD") (pinfunction "PAD_PAD") (pintype "power_in"))
      (node (ref "IC11") (pin "4") (pinfunction "GND_4") (pintype "passive"))
      (node (ref "IC11") (pin "PAD") (pinfunction "PAD_PAD") (pintype "passive"))
      (node (ref "IC11A") (pin "4") (pinfunction "GND_4") (pintype "passive"))
      (node (ref "IC12") (pin "12") (pinfunction "GND_12") (pintype "passive"))
      (node (ref "IC12") (pin "6") (pinfunction "GND_6") (pintype "passive"))
      (node (ref "IC13") (pin "12") (pinfunction "GND_12") (pintype "passive"))
      (node (ref "IC13") (pin "6") (pinfunction "GND_6") (pintype "passive"))
      (node (ref "IC14") (pin "2") (pinfunction "GND_2") (pintype "passive"))
      (node (ref "IC14") (pin "PAD") (pinfunction "PAD_PAD") (pintype "passive"))
      (node (ref "IC7") (pin "1") (pinfunction "GND_1") (pintype "passive"))
      (node (ref "IC7") (pin "11") (pinfunction "GND_11") (pintype "passive"))
      (node (ref "IC7") (pin "12") (pinfunction "GND_12") (pintype "passive"))
      (node (ref "IC7") (pin "16") (pinfunction "GND_16") (pintype "passive"))
      (node (ref "IC7") (pin "19") (pinfunction "GND_19") (pintype "passive"))
      (node (ref "IC7") (pin "22") (pinfunction "SEL_22") (pintype "passive"))
      (node (ref "IC7") (pin "25") (pinfunction "GND_25") (pintype "passive"))
      (node (ref "IC7") (pin "7") (pinfunction "GND_7") (pintype "passive"))
      (node (ref "IC8") (pin "4") (pinfunction "GND_4") (pintype "passive"))
      (node (ref "IC8") (pin "5") (pinfunction "A2_5") (pintype "passive"))
      (node (ref "IC8") (pin "6") (pinfunction "A1_6") (pintype "passive"))
      (node (ref "IC8") (pin "7") (pinfunction "A0_7") (pintype "passive"))
      (node (ref "IC9") (pin "5") (pinfunction "GND_5") (pintype "power_in"))
      (node (ref "J8") (pin "2") (pinfunction "Y_2") (pintype "passive"))
      (node (ref "J9") (pin "2") (pinfunction "Y_2") (pintype "passive"))
      (node (ref "MECH11") (pin "1") (pinfunction "GND_1") (pintype "passive"))
      (node (ref "MECH12") (pin "1") (pinfunction "GND_1") (pintype "passive"))
      (node (ref "MECH13") (pin "1") (pinfunction "GND_1") (pintype "passive"))
      (node (ref "MECH14") (pin "1") (pinfunction "GND_1") (pintype "passive"))
      (node (ref "R63") (pin "1") (pinfunction "1_1") (pintype "passive"))
      (node (ref "R68") (pin "2") (pinfunction "2_2") (pintype "passive"))
      (node (ref "R74") (pin "1") (pinfunction "1_1") (pintype "passive"))
      (node (ref "R81") (pin "2") (pinfunction "2_2") (pintype "passive"))
      (node (ref "R83") (pin "1") (pinfunction "1_1") (pintype "passive"))
      (node (ref "R85") (pin "1") (pinfunction "1_1") (pintype "passive"))
      (node (ref "VT4") (pin "S") (pinfunction "S_S") (pintype "passive"))
      (node (ref "XO1") (pin "4") (pinfunction "GND_4") (pintype "passive"))
    )
    (net (code "26") (name "Net-(C148-Pad1)") (class "Default")
      (node (ref "C148") (pin "1") (pinfunction "1_1") (pintype "passive"))
      (node (ref "C149") (pin "2") (pinfunction "2_2") (pintype "passive"))
      (node (ref "R63") (pin "2") (pinfunction "2_2") (pintype "passive"))
    )
    (net (code "27") (name "Net-(C148-Pad2)") (class "Default")
      (node (ref "C148") (pin "2") (pinfunction "2_2") (pintype "passive"))
      (node (ref "R59") (pin "2") (pinfunction "2_2") (pintype "passive"))
      (node (ref "R62") (pin "2") (pinfunction "2_2") (pintype "passive"))
    )
    (net (code "28") (name "Net-(C153-Pad2)") (class "Default")
      (node (ref "C153") (pin "2") (pinfunction "2_2") (pintype "passive"))
      (node (ref "FR15") (pin "1") (pinfunction "1_1") (pintype "passive"))
      (node (ref "R60") (pin "1") (pinfunction "1_1") (pintype "passive"))
    )
    (net (code "29") (name "Net-(C172-Pad1)") (class "Default")
      (node (ref "C172") (pin "1") (pinfunction "1_1") (pintype "passive"))
      (node (ref "J10") (pin "2") (pinfunction "2_2") (pintype "passive"))
      (node (ref "R69") (pin "2") (pinfunction "2_2") (pintype "passive"))
      (node (ref "R71") (pin "2") (pinfunction "2_2") (pintype "passive"))
    )
    (net (code "30") (name "Net-(IC7-CLKin)") (class "Default")
      (node (ref "C149") (pin "1") (pinfunction "1_1") (pintype "passive"))
      (node (ref "IC7") (pin "21") (pinfunction "CLKin_21") (pintype "passive"))
    )
    (net (code "31") (name "Net-(IC7-CLKin*)") (class "Default")
      (node (ref "C156") (pin "2") (pinfunction "2_2") (pintype "passive"))
      (node (ref "IC7") (pin "20") (pinfunction "CLKin*_20") (pintype "passive"))
    )
    (net (code "32") (name "Net-(IC7-CLKout0)") (class "Default")
      (node (ref "IC7") (pin "3") (pinfunction "CLKout0_3") (pintype "passive"))
      (node (ref "R61") (pin "2") (pinfunction "2_2") (pintype "passive"))
    )
    (net (code "33") (name "Net-(IC7-CLKout1)") (class "Default")
      (node (ref "IC7") (pin "5") (pinfunction "CLKout1_5") (pintype "passive"))
      (node (ref "R65") (pin "2") (pinfunction "2_2") (pintype "passive"))
    )
    (net (code "34") (name "Net-(IC7-OE)") (class "Default")
      (node (ref "IC7") (pin "24") (pinfunction "OE_24") (pintype "passive"))
      (node (ref "R57") (pin "1") (pinfunction "1_1") (pintype "passive"))
    )
    (net (code "35") (name "Net-(IC9-VDD)") (class "Default")
      (node (ref "C163") (pin "1") (pinfunction "1_1") (pintype "passive"))
      (node (ref "FR17") (pin "2") (pinfunction "2_2") (pintype "passive"))
      (node (ref "IC9") (pin "4") (pinfunction "VDD_4") (pintype "power_in"))
    )
    (net (code "36") (name "Net-(IC9-VOUT)") (class "Default")
      (node (ref "IC9") (pin "6") (pinfunction "VOUT_6") (pintype "tri_state"))
      (node (ref "R67") (pin "2") (pinfunction "2_2") (pintype "passive"))
    )
    (net (code "37") (name "Net-(IC12-FB)") (class "Default")
      (node (ref "IC12") (pin "11") (pinfunction "FB_11") (pintype "passive"))
      (node (ref "R83") (pin "2") (pinfunction "2_2") (pintype "passive"))
    )
    (net (code "38") (name "Net-(IC13-EN)") (class "Default")
      (node (ref "IC13") (pin "1") (pinfunction "EN_1") (pintype "passive"))
      (node (ref "R82") (pin "1") (pinfunction "1_1") (pintype "passive"))
      (node (ref "R84") (pin "2") (pinfunction "2_2") (pintype "passive"))
    )
    (net (code "39") (name "Net-(IC13-FB)") (class "Default")
      (node (ref "IC13") (pin "11") (pinfunction "FB_11") (pintype "passive"))
      (node (ref "R85") (pin "2") (pinfunction "2_2") (pintype "passive"))
    )
    (net (code "40") (name "Net-(IC13-PG)") (class "Default")
      (node (ref "IC13") (pin "10") (pinfunction "PG_10") (pintype "passive"))
      (node (ref "R78") (pin "1") (pinfunction "1_1") (pintype "passive"))
    )
    (net (code "41") (name "Net-(IC14-ADJ)") (class "Default")
      (node (ref "IC14") (pin "5") (pinfunction "ADJ_5") (pintype "input"))
      (node (ref "R80") (pin "1") (pinfunction "1_1") (pintype "passive"))
      (node (ref "R81") (pin "1") (pinfunction "1_1") (pintype "passive"))
    )
    (net (code "42") (name "Net-(IC14-PG)") (class "Default")
      (node (ref "C183") (pin "2") (pinfunction "2_2") (pintype "passive"))
      (node (ref "IC14") (pin "3") (pinfunction "PG_3") (pintype "output"))
    )
    (net (code "43") (name "Net-(IC14-Vout)") (class "Default")
      (node (ref "IC14") (pin "4") (pinfunction "Vout_4") (pintype "output"))
      (node (ref "R79") (pin "1") (pinfunction "1_1") (pintype "passive"))
      (node (ref "R80") (pin "2") (pinfunction "2_2") (pintype "passive"))
    )
    (net (code "44") (name "Net-(J10-Pad1)") (class "Default")
      (node (ref "J10") (pin "1") (pinfunction "1_1") (pintype "passive"))
      (node (ref "R74") (pin "2") (pinfunction "2_2") (pintype "passive"))
      (node (ref "VT4") (pin "D") (pinfunction "D_D") (pintype "passive"))
    )
    (net (code "45") (name "Net-(LED1-Pad3)") (class "Default")
      (node (ref "LED1") (pin "3") (pinfunction "3_3") (pintype "power_in"))
      (node (ref "R70") (pin "1") (pinfunction "1_1") (pintype "passive"))
    )
    (net (code "46") (name "Net-(LED1-Pad4)") (class "Default")
      (node (ref "LED1") (pin "4") (pinfunction "4_4") (pintype "power_in"))
      (node (ref "R72") (pin "1") (pinfunction "1_1") (pintype "passive"))
    )
    (net (code "47") (name "Net-(LED2-PadC1)") (class "Default")
      (node (ref "LED2") (pin "C1") (pinfunction "C1_C1") (pintype "power_in"))
      (node (ref "R75") (pin "1") (pinfunction "1_1") (pintype "passive"))
    )
    (net (code "48") (name "Net-(LED2-PadC2)") (class "Default")
      (node (ref "LED2") (pin "C2") (pinfunction "C2_C2") (pintype "power_in"))
      (node (ref "R73") (pin "1") (pinfunction "1_1") (pintype "passive"))
    )
    (net (code "49") (name "Net-(XO1-RF_OUT)") (class "Default")
      (node (ref "R59") (pin "1") (pinfunction "1_1") (pintype "passive"))
      (node (ref "XO1") (pin "6") (pinfunction "RF_OUT_6") (pintype "output"))
    )
    (net (code "50") (name "Net-(XO1-VCC)") (class "Default")
      (node (ref "C155") (pin "2") (pinfunction "2_2") (pintype "passive"))
      (node (ref "FR15") (pin "2") (pinfunction "2_2") (pintype "passive"))
      (node (ref "XO1") (pin "9") (pinfunction "VCC_9") (pintype "power_in"))
    )
    (net (code "51") (name "Net-(XO1-VC_FILTER)") (class "Default")
      (node (ref "C151") (pin "2") (pinfunction "2_2") (pintype "passive"))
      (node (ref "XO1") (pin "7") (pinfunction "VC_FILTER_7") (pintype "input"))
    )
    (net (code "52") (name "VCC1P8") (class "Default")
      (node (ref "C174") (pin "1") (pinfunction "1_1") (pintype "passive"))
      (node (ref "C181") (pin "2") (pinfunction "2_2") (pintype "passive"))
      (node (ref "FR16") (pin "1") (pinfunction "1_1") (pintype "passive"))
      (node (ref "FR20") (pin "1") (pinfunction "1_1") (pintype "passive"))
      (node (ref "IC11") (pin "8") (pinfunction "VCC_8") (pintype "power_in"))
      (node (ref "IC11A") (pin "8") (pinfunction "VCC_8") (pintype "passive"))
      (node (ref "IC12") (pin "7") (pinfunction "VOUT_7") (pintype "passive"))
      (node (ref "IC12") (pin "8") (pinfunction "VOUT_8") (pintype "passive"))
      (node (ref "R58") (pin "2") (pinfunction "2_2") (pintype "passive"))
    )
    (net (code "53") (name "VCC1P8_LMS") (class "Default")
      (node (ref "C175") (pin "2") (pinfunction "2_2") (pintype "passive"))
      (node (ref "FR20") (pin "2") (pinfunction "2_2") (pintype "passive"))
    )
    (net (code "54") (name "VCC3P3") (class "Default")
      (node (ref "C150") (pin "1") (pinfunction "1_1") (pintype "passive"))
      (node (ref "C162") (pin "1") (pinfunction "1_1") (pintype "passive"))
      (node (ref "C178") (pin "2") (pinfunction "2_2") (pintype "passive"))
      (node (ref "C182") (pin "2") (pinfunction "2_2") (pintype "passive"))
      (node (ref "FR22") (pin "1") (pinfunction "1_1") (pintype "passive"))
      (node (ref "IC10") (pin "8") (pinfunction "VCC_8") (pintype "power_in"))
      (node (ref "IC13") (pin "7") (pinfunction "VOUT_7") (pintype "passive"))
      (node (ref "IC13") (pin "8") (pinfunction "VOUT_8") (pintype "passive"))
      (node (ref "IC14") (pin "1") (pinfunction "EN_1") (pintype "input"))
      (node (ref "IC14") (pin "6") (pinfunction "Vin_6") (pintype "input"))
      (node (ref "IC8") (pin "8") (pinfunction "VCC_8") (pintype "passive"))
      (node (ref "LED1") (pin "1") (pinfunction "1_1") (pintype "power_in"))
      (node (ref "LED1") (pin "2") (pinfunction "2_2") (pintype "power_in"))
      (node (ref "LED2") (pin "A") (pinfunction "A_A") (pintype "power_in"))
      (node (ref "R64") (pin "1") (pinfunction "1_1") (pintype "passive"))
      (node (ref "R66") (pin "1") (pinfunction "1_1") (pintype "passive"))
      (node (ref "R71") (pin "1") (pinfunction "1_1") (pintype "passive"))
      (node (ref "R77") (pin "1") (pinfunction "1_1") (pintype "passive"))
    )
    (net (code "55") (name "VCC3P3_CLK") (class "Default")
      (node (ref "C184") (pin "2") (pinfunction "2_2") (pintype "passive"))
      (node (ref "FR17") (pin "1") (pinfunction "1_1") (pintype "passive"))
      (node (ref "FR19") (pin "1") (pinfunction "1_1") (pintype "passive"))
      (node (ref "FR22") (pin "2") (pinfunction "2_2") (pintype "passive"))
      (node (ref "R60") (pin "2") (pinfunction "2_2") (pintype "passive"))
    )
    (net (code "56") (name "VCC5P0_USB") (class "Default")
      (node (ref "C176") (pin "2") (pinfunction "2_2") (pintype "passive"))
      (node (ref "C177") (pin "2") (pinfunction "2_2") (pintype "passive"))
      (node (ref "IC12") (pin "1") (pinfunction "EN_1") (pintype "passive"))
      (node (ref "IC12") (pin "4") (pinfunction "VIN_4") (pintype "passive"))
      (node (ref "IC12") (pin "5") (pinfunction "VIN_5") (pintype "passive"))
      (node (ref "IC13") (pin "4") (pinfunction "VIN_4") (pintype "passive"))
      (node (ref "IC13") (pin "5") (pinfunction "VIN_5") (pintype "passive"))
      (node (ref "R69") (pin "1") (pinfunction "1_1") (pintype "passive"))
      (node (ref "R76") (pin "2") (pinfunction "2_2") (pintype "passive"))
      (node (ref "R78") (pin "2") (pinfunction "2_2") (pintype "passive"))
      (node (ref "R84") (pin "1") (pinfunction "1_1") (pintype "passive"))
    )
    (net (code "57") (name "VDIO_LMS") (class "Default")
      (node (ref "C180") (pin "2") (pinfunction "2_2") (pintype "passive"))
      (node (ref "FR21") (pin "2") (pinfunction "2_2") (pintype "passive"))
    )
    (net (code "58") (name "VDIO_LMS_FPGA") (class "Default")
      (node (ref "C179") (pin "2") (pinfunction "2_2") (pintype "passive"))
      (node (ref "FR18") (pin "1") (pinfunction "1_1") (pintype "passive"))
      (node (ref "FR21") (pin "1") (pinfunction "1_1") (pintype "passive"))
      (node (ref "R77") (pin "2") (pinfunction "2_2") (pintype "passive"))
      (node (ref "R79") (pin "2") (pinfunction "2_2") (pintype "passive"))
    )
    (net (code "59") (name "VDIO_LMS_LMK") (class "Default")
      (node (ref "C164") (pin "2") (pinfunction "2_2") (pintype "passive"))
      (node (ref "C165") (pin "2") (pinfunction "2_2") (pintype "passive"))
      (node (ref "C166") (pin "2") (pinfunction "2_2") (pintype "passive"))
      (node (ref "C167") (pin "2") (pinfunction "2_2") (pintype "passive"))
      (node (ref "FR18") (pin "2") (pinfunction "2_2") (pintype "passive"))
      (node (ref "IC7") (pin "14") (pinfunction "Vddo_14") (pintype "passive"))
      (node (ref "IC7") (pin "18") (pinfunction "Vddo_18") (pintype "passive"))
    )
    (net (code "60") (name "unconnected-(FAN1-STANDS-Pad1)") (class "Default")
      (node (ref "FAN1") (pin "1") (pinfunction "STANDS_1") (pintype "passive+no_connect"))
    )
    (net (code "61") (name "unconnected-(IC7-CLKout3-Pad15)") (class "Default")
      (node (ref "IC7") (pin "15") (pinfunction "CLKout3_15") (pintype "passive+no_connect"))
    )
    (net (code "62") (name "unconnected-(IC7-OSCin-Pad9)") (class "Default")
      (node (ref "IC7") (pin "9") (pinfunction "OSCin_9") (pintype "passive+no_connect"))
    )
    (net (code "63") (name "unconnected-(IC7-OSCout-Pad10)") (class "Default")
      (node (ref "IC7") (pin "10") (pinfunction "OSCout_10") (pintype "passive+no_connect"))
    )
    (net (code "64") (name "unconnected-(IC12-NC-Pad2)") (class "Default")
      (node (ref "IC12") (pin "2") (pinfunction "NC_2") (pintype "passive+no_connect"))
    )
    (net (code "65") (name "unconnected-(IC12-NC-Pad3)") (class "Default")
      (node (ref "IC12") (pin "3") (pinfunction "NC_3") (pintype "passive+no_connect"))
    )
    (net (code "66") (name "unconnected-(IC12-NC-Pad9)") (class "Default")
      (node (ref "IC12") (pin "9") (pinfunction "NC_9") (pintype "passive+no_connect"))
    )
    (net (code "67") (name "unconnected-(IC12-NC-Pad13)") (class "Default")
      (node (ref "IC12") (pin "13") (pinfunction "NC_13") (pintype "passive+no_connect"))
    )
    (net (code "68") (name "unconnected-(IC12-NC-Pad14)") (class "Default")
      (node (ref "IC12") (pin "14") (pinfunction "NC_14") (pintype "passive+no_connect"))
    )
    (net (code "69") (name "unconnected-(IC13-NC-Pad2)") (class "Default")
      (node (ref "IC13") (pin "2") (pinfunction "NC_2") (pintype "passive+no_connect"))
    )
    (net (code "70") (name "unconnected-(IC13-NC-Pad3)") (class "Default")
      (node (ref "IC13") (pin "3") (pinfunction "NC_3") (pintype "passive+no_connect"))
    )
    (net (code "71") (name "unconnected-(IC13-NC-Pad9)") (class "Default")
      (node (ref "IC13") (pin "9") (pinfunction "NC_9") (pintype "passive+no_connect"))
    )
    (net (code "72") (name "unconnected-(IC13-NC-Pad13)") (class "Default")
      (node (ref "IC13") (pin "13") (pinfunction "NC_13") (pintype "passive+no_connect"))
    )
    (net (code "73") (name "unconnected-(IC13-NC-Pad14)") (class "Default")
      (node (ref "IC13") (pin "14") (pinfunction "NC_14") (pintype "passive+no_connect"))
    )
    (net (code "74") (name "unconnected-(MECH16-PadMH1)") (class "Default")
      (node (ref "MECH16") (pin "MH1") (pinfunction "MH1_MH1") (pintype "passive+no_connect"))
    )
    (net (code "75") (name "unconnected-(MECH17-PadMH1)") (class "Default")
      (node (ref "MECH17") (pin "MH1") (pinfunction "MH1_MH1") (pintype "passive+no_connect"))
    )
    (net (code "76") (name "unconnected-(MECH18-PadMH1)") (class "Default")
      (node (ref "MECH18") (pin "MH1") (pinfunction "MH1_MH1") (pintype "passive+no_connect"))
    )
    (net (code "77") (name "unconnected-(MECH19-PadMH1)") (class "Default")
      (node (ref "MECH19") (pin "MH1") (pinfunction "MH1_MH1") (pintype "passive+no_connect"))
    )
    (net (code "78") (name "unconnected-(MECH20-PadMH1)") (class "Default")
      (node (ref "MECH20") (pin "MH1") (pinfunction "MH1_MH1") (pintype "passive+no_connect"))
    )
    (net (code "79") (name "unconnected-(MECH21-PadMH1)") (class "Default")
      (node (ref "MECH21") (pin "MH1") (pinfunction "MH1_MH1") (pintype "passive+no_connect"))
    )
    (net (code "80") (name "unconnected-(XO1-NC-Pad2)") (class "Default")
      (node (ref "XO1") (pin "2") (pinfunction "NC_2") (pintype "passive+no_connect"))
    )
    (net (code "81") (name "unconnected-(XO1-NC-Pad3)") (class "Default")
      (node (ref "XO1") (pin "3") (pinfunction "NC_3") (pintype "passive+no_connect"))
    )
    (net (code "82") (name "unconnected-(XO1-NC-Pad5)") (class "Default")
      (node (ref "XO1") (pin "5") (pinfunction "NC_5") (pintype "passive+no_connect"))
    )
    (net (code "83") (name "unconnected-(XO1-NC-Pad8)") (class "Default")
      (node (ref "XO1") (pin "8") (pinfunction "NC_8") (pintype "passive+no_connect"))
    )
    (net (code "84") (name "unconnected-(XO1-NC-Pad10)") (class "Default")
      (node (ref "XO1") (pin "10") (pinfunction "NC_10") (pintype "passive+no_connect"))
    )
  )
)
